# RH020_1.net
KiCad netlist of a schematic drawn in EAGLE
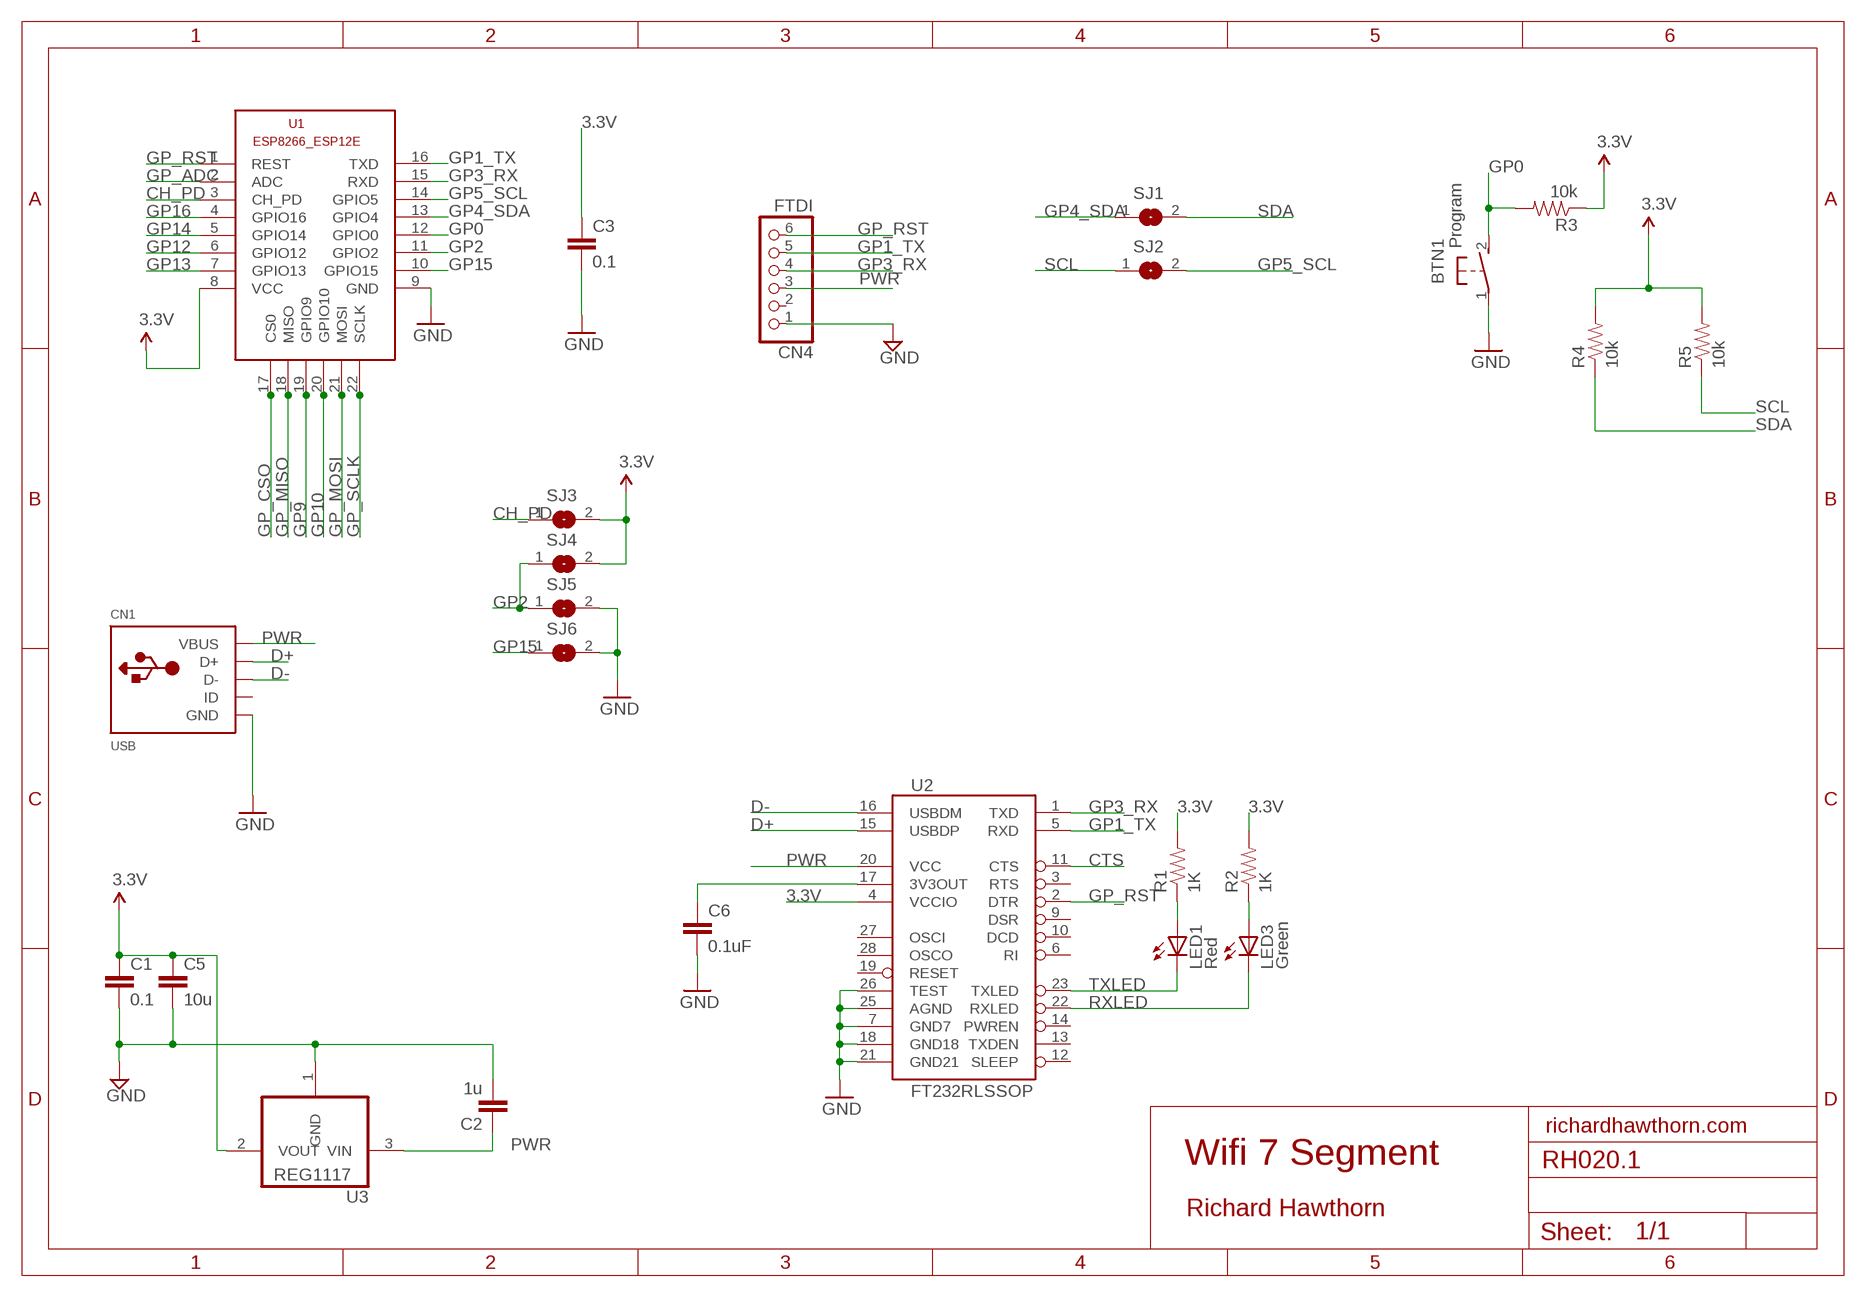
[diagram p0: schematic, sheet 1, part 1 of 2]
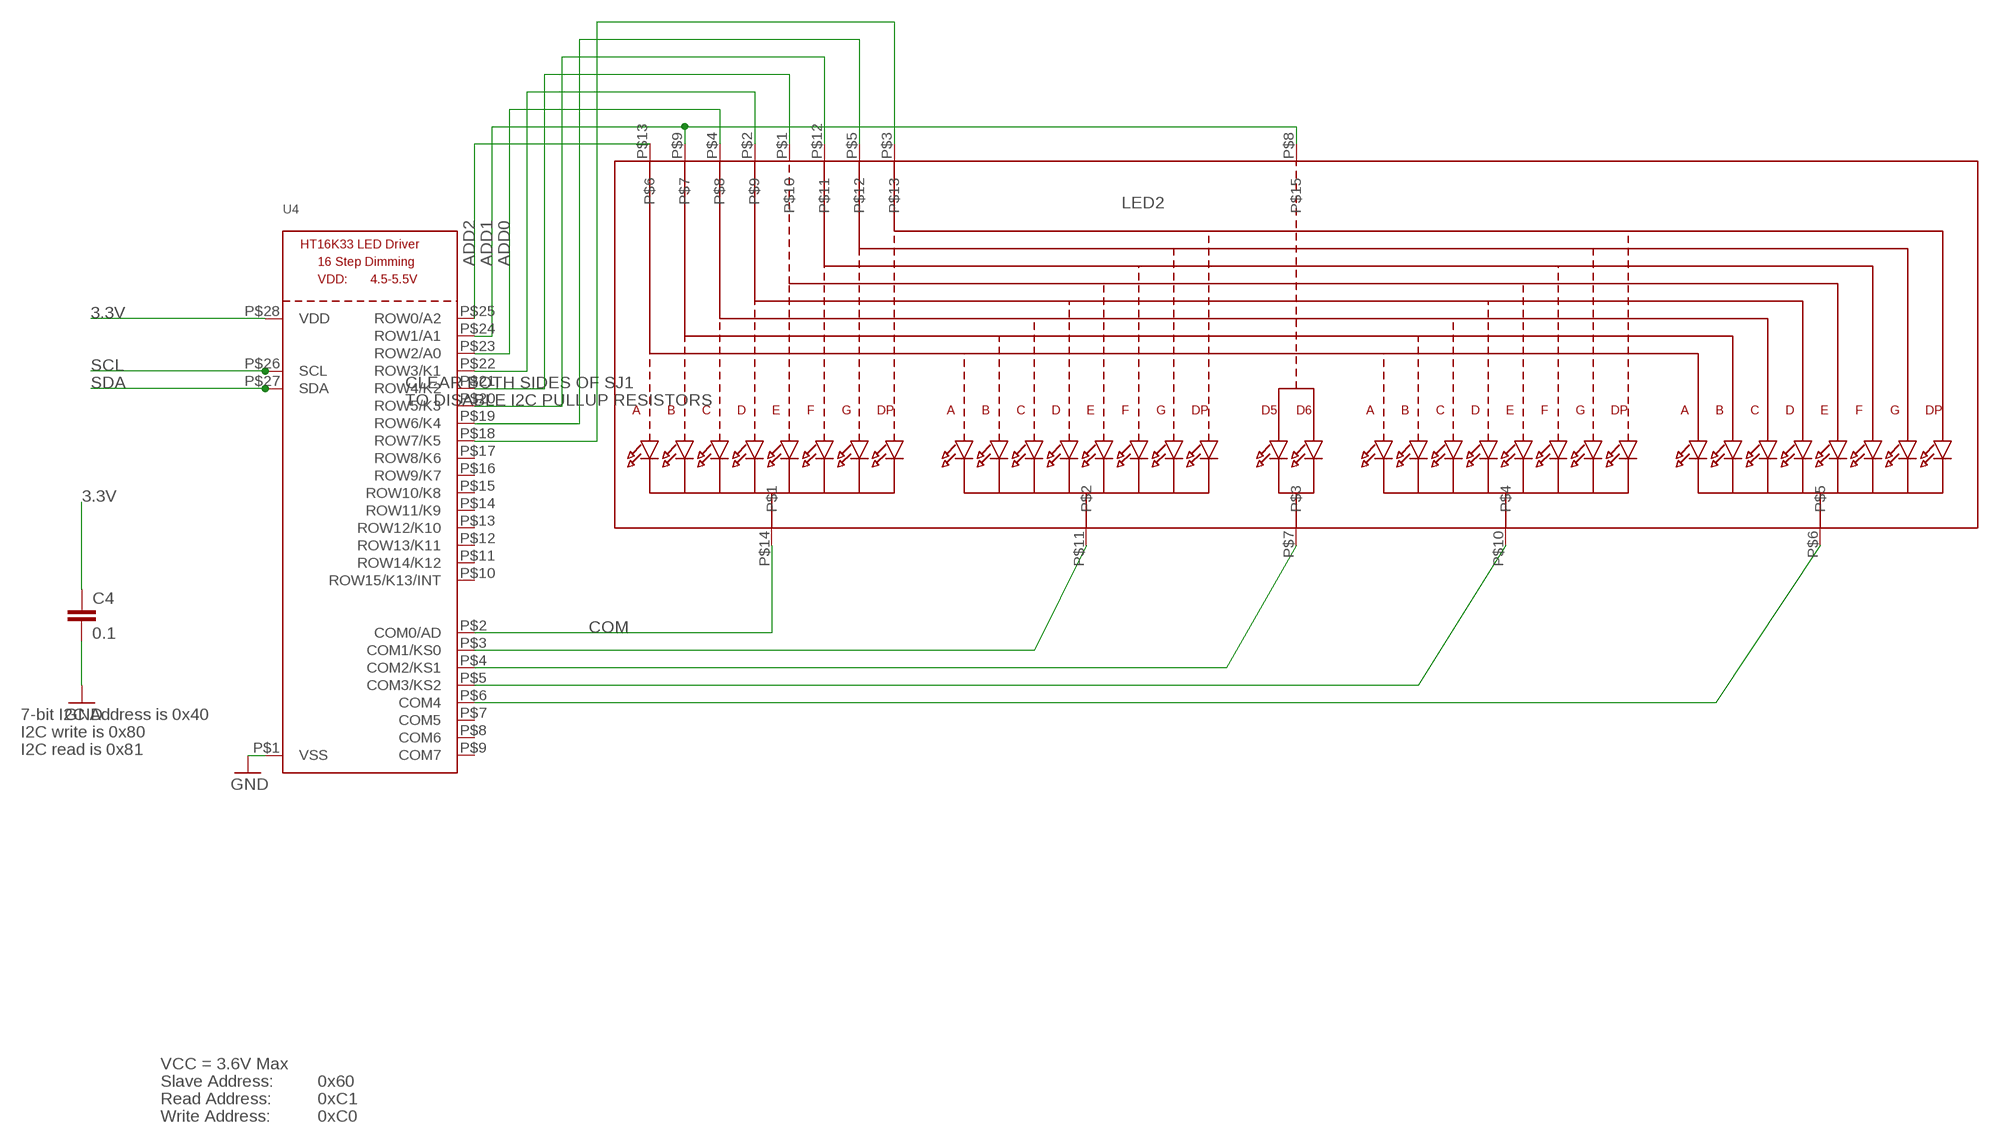
[diagram p1: schematic, sheet 1, part 2 of 2]

(export (version "E")
  (design (tool "Eeschema 10.0.6"))
  (components
    (comp (ref "BTN1")
      (value "Program")
      (footprint "eagle-import:DTS-3")
      (libsource (lib "eagle-import") (part "DTS-3"))
    )
    (comp (ref "C1")
      (value "0.1")
      (footprint "eagle-import:0603-CAP")
      (libsource (lib "eagle-import") (part "CAP0603-CAP"))
    )
    (comp (ref "C2")
      (value "1u")
      (footprint "eagle-import:0603-CAP")
      (libsource (lib "eagle-import") (part "CAP0603-CAP"))
    )
    (comp (ref "C3")
      (value "0.1")
      (footprint "eagle-import:0603-CAP")
      (libsource (lib "eagle-import") (part "CAP0603-CAP"))
    )
    (comp (ref "C4")
      (value "0.1")
      (footprint "eagle-import:0603-CAP")
      (libsource (lib "eagle-import") (part "CAP0603-CAP"))
    )
    (comp (ref "C5")
      (value "10u")
      (footprint "eagle-import:0805-CAP")
      (libsource (lib "eagle-import") (part "CAP0805-CAP"))
    )
    (comp (ref "C6")
      (value "0.1uF")
      (footprint "eagle-import:0402-CAP")
      (libsource (lib "eagle-import") (part "SparkFun_CAP0402-CAP"))
    )
    (comp (ref "CN1")
      (value "USB")
      (footprint "eagle-import:USB-MINIB")
      (libsource (lib "eagle-import") (part "USBMINIB"))
    )
    (comp (ref "CN4")
      (value "FTDI")
      (footprint "eagle-import:1X06")
      (libsource (lib "eagle-import") (part "PINHD-1X6"))
    )
    (comp (ref "LED1")
      (value "Red")
      (footprint "eagle-import:LED-0603")
      (libsource (lib "eagle-import") (part "LED0603"))
    )
    (comp (ref "LED2")
      (value "DISP_SEGMENT_4DIGIT_BL-Q56C43")
      (footprint "eagle-import:SEGMENT-BL-Q56C43")
      (libsource (lib "eagle-import") (part "DISP_SEGMENT_4DIGIT_BL-Q56C43"))
    )
    (comp (ref "LED3")
      (value "Green")
      (footprint "eagle-import:LED-0603")
      (libsource (lib "eagle-import") (part "LED0603"))
    )
    (comp (ref "R1")
      (value "1K")
      (footprint "eagle-import:0402-RES")
      (libsource (lib "eagle-import") (part "RESISTOR0402-RES"))
    )
    (comp (ref "R2")
      (value "1K")
      (footprint "eagle-import:0402-RES")
      (libsource (lib "eagle-import") (part "RESISTOR0402-RES"))
    )
    (comp (ref "R3")
      (value "10k")
      (footprint "eagle-import:0805")
      (libsource (lib "eagle-import") (part "RESISTOR0805-RES"))
    )
    (comp (ref "R4")
      (value "10k")
      (footprint "eagle-import:0805")
      (libsource (lib "eagle-import") (part "RESISTOR0805-RES"))
    )
    (comp (ref "R5")
      (value "10k")
      (footprint "eagle-import:0805")
      (libsource (lib "eagle-import") (part "RESISTOR0805-RES"))
    )
    (comp (ref "SJ1") (value "SJ") (footprint "eagle-import:SJ") (libsource (lib "eagle-import") (part "SJ")))
    (comp (ref "SJ2") (value "SJ") (footprint "eagle-import:SJ") (libsource (lib "eagle-import") (part "SJ")))
    (comp (ref "SJ3") (value "SJ") (footprint "eagle-import:SJ") (libsource (lib "eagle-import") (part "SJ")))
    (comp (ref "SJ4") (value "SJ") (footprint "eagle-import:SJ") (libsource (lib "eagle-import") (part "SJ")))
    (comp (ref "SJ5") (value "SJ") (footprint "eagle-import:SJ") (libsource (lib "eagle-import") (part "SJ")))
    (comp (ref "SJ6") (value "SJ") (footprint "eagle-import:SJ") (libsource (lib "eagle-import") (part "SJ")))
    (comp (ref "U1")
      (value "ESP8266-12EESP8266-ESP12E")
      (footprint "eagle-import:ESP8266-ESP12E")
      (libsource (lib "eagle-import") (part "ESP8266-12EESP8266-ESP12E"))
    )
    (comp (ref "U2")
      (value "FT232RLSSOP")
      (footprint "eagle-import:SSOP28DB")
      (libsource (lib "eagle-import") (part "FT232RLSSOP"))
    )
    (comp (ref "U3")
      (value "REG1117")
      (footprint "eagle-import:SOT223")
      (libsource (lib "eagle-import") (part "REG1117"))
    )
    (comp (ref "U4")
      (value "HT16K33_SOP28")
      (footprint "eagle-import:SOP28_300MIL")
      (libsource (lib "eagle-import") (part "HT16K33_SOP28"))
    )
  )
  (nets
    (net (code "1") (name "/ADD0") (class "Default")
      (node (ref "LED2") (pin "P$4") (pinfunction "P$8_P$4") (pintype "bidirectional"))
      (node (ref "U4") (pin "P$23") (pinfunction "ROW2/A0_P$23") (pintype "bidirectional"))
    )
    (net (code "2") (name "/ADD1") (class "Default")
      (node (ref "LED2") (pin "P$8") (pinfunction "P$15_P$8") (pintype "bidirectional"))
      (node (ref "LED2") (pin "P$9") (pinfunction "P$7_P$9") (pintype "bidirectional"))
      (node (ref "U4") (pin "P$24") (pinfunction "ROW1/A1_P$24") (pintype "bidirectional"))
    )
    (net (code "3") (name "/ADD2") (class "Default")
      (node (ref "LED2") (pin "P$13") (pinfunction "P$6_P$13") (pintype "bidirectional"))
      (node (ref "U4") (pin "P$25") (pinfunction "ROW0/A2_P$25") (pintype "bidirectional"))
    )
    (net (code "4") (name "/CH_PD") (class "Default")
      (node (ref "SJ3") (pin "1") (pinfunction "1_1") (pintype "passive"))
      (node (ref "U1") (pin "3") (pinfunction "CH_PD_3") (pintype "bidirectional"))
    )
    (net (code "5") (name "/COM") (class "Default")
      (node (ref "LED2") (pin "P$14") (pinfunction "P$1_P$14") (pintype "bidirectional"))
      (node (ref "U4") (pin "P$2") (pinfunction "COM0/AD_P$2") (pintype "bidirectional"))
    )
    (net (code "6") (name "/CTS") (class "Default")
      (node (ref "U2") (pin "11") (pinfunction "CTS_11") (pintype "input"))
    )
    (net (code "7") (name "/D+") (class "Default")
      (node (ref "CN1") (pin "D+") (pinfunction "D+_D+") (pintype "bidirectional"))
      (node (ref "U2") (pin "15") (pinfunction "USBDP_15") (pintype "bidirectional"))
    )
    (net (code "8") (name "/D-") (class "Default")
      (node (ref "CN1") (pin "D-") (pinfunction "D-_D-") (pintype "bidirectional"))
      (node (ref "U2") (pin "16") (pinfunction "USBDM_16") (pintype "bidirectional"))
    )
    (net (code "9") (name "/GP0") (class "Default")
      (node (ref "BTN1") (pin "2") (pinfunction "2_2") (pintype "passive"))
      (node (ref "R3") (pin "2") (pinfunction "2_2") (pintype "passive"))
      (node (ref "U1") (pin "12") (pinfunction "GPIO0_12") (pintype "bidirectional"))
    )
    (net (code "10") (name "/GP1_TX") (class "Default")
      (node (ref "CN4") (pin "5") (pinfunction "5_5") (pintype "passive"))
      (node (ref "U1") (pin "16") (pinfunction "TXD_16") (pintype "bidirectional"))
      (node (ref "U2") (pin "5") (pinfunction "RXD_5") (pintype "input"))
    )
    (net (code "11") (name "/GP2") (class "Default")
      (node (ref "SJ4") (pin "1") (pinfunction "1_1") (pintype "passive"))
      (node (ref "SJ5") (pin "1") (pinfunction "1_1") (pintype "passive"))
      (node (ref "U1") (pin "11") (pinfunction "GPIO2_11") (pintype "bidirectional"))
    )
    (net (code "12") (name "/GP3_RX") (class "Default")
      (node (ref "CN4") (pin "4") (pinfunction "4_4") (pintype "passive"))
      (node (ref "U1") (pin "15") (pinfunction "RXD_15") (pintype "bidirectional"))
      (node (ref "U2") (pin "1") (pinfunction "TXD_1") (pintype "output"))
    )
    (net (code "13") (name "/GP4_SDA") (class "Default")
      (node (ref "SJ1") (pin "1") (pinfunction "1_1") (pintype "passive"))
      (node (ref "U1") (pin "13") (pinfunction "GPIO4_13") (pintype "bidirectional"))
    )
    (net (code "14") (name "/GP5_SCL") (class "Default")
      (node (ref "SJ2") (pin "2") (pinfunction "2_2") (pintype "passive"))
      (node (ref "U1") (pin "14") (pinfunction "GPIO5_14") (pintype "bidirectional"))
    )
    (net (code "15") (name "/GP9") (class "Default")
      (node (ref "U1") (pin "19") (pinfunction "GPIO9_19") (pintype "bidirectional"))
    )
    (net (code "16") (name "/GP10") (class "Default")
      (node (ref "U1") (pin "20") (pinfunction "GPIO10_20") (pintype "bidirectional"))
    )
    (net (code "17") (name "/GP12") (class "Default")
      (node (ref "U1") (pin "6") (pinfunction "GPIO12_6") (pintype "bidirectional"))
    )
    (net (code "18") (name "/GP13") (class "Default")
      (node (ref "U1") (pin "7") (pinfunction "GPIO13_7") (pintype "bidirectional"))
    )
    (net (code "19") (name "/GP14") (class "Default")
      (node (ref "U1") (pin "5") (pinfunction "GPIO14_5") (pintype "bidirectional"))
    )
    (net (code "20") (name "/GP15") (class "Default")
      (node (ref "SJ6") (pin "1") (pinfunction "1_1") (pintype "passive"))
      (node (ref "U1") (pin "10") (pinfunction "GPIO15_10") (pintype "bidirectional"))
    )
    (net (code "21") (name "/GP16") (class "Default")
      (node (ref "U1") (pin "4") (pinfunction "GPIO16_4") (pintype "bidirectional"))
    )
    (net (code "22") (name "/GP_ADC") (class "Default")
      (node (ref "U1") (pin "2") (pinfunction "ADC_2") (pintype "bidirectional"))
    )
    (net (code "23") (name "/GP_CSO") (class "Default")
      (node (ref "U1") (pin "17") (pinfunction "CS0_17") (pintype "bidirectional"))
    )
    (net (code "24") (name "/GP_MISO") (class "Default")
      (node (ref "U1") (pin "18") (pinfunction "MISO_18") (pintype "bidirectional"))
    )
    (net (code "25") (name "/GP_MOSI") (class "Default")
      (node (ref "U1") (pin "21") (pinfunction "MOSI_21") (pintype "bidirectional"))
    )
    (net (code "26") (name "/GP_RST") (class "Default")
      (node (ref "CN4") (pin "6") (pinfunction "6_6") (pintype "passive"))
      (node (ref "U1") (pin "1") (pinfunction "REST_1") (pintype "bidirectional"))
      (node (ref "U2") (pin "2") (pinfunction "DTR_2") (pintype "output"))
    )
    (net (code "27") (name "/GP_SCLK") (class "Default")
      (node (ref "U1") (pin "22") (pinfunction "SCLK_22") (pintype "bidirectional"))
    )
    (net (code "28") (name "/PWR") (class "Default")
      (node (ref "C2") (pin "1") (pinfunction "1_1") (pintype "passive"))
      (node (ref "CN1") (pin "VBUS") (pinfunction "VBUS_VBUS") (pintype "power_in"))
      (node (ref "CN4") (pin "3") (pinfunction "3_3") (pintype "passive"))
      (node (ref "U2") (pin "20") (pinfunction "VCC_20") (pintype "power_in"))
      (node (ref "U3") (pin "3") (pinfunction "VIN_3") (pintype "input"))
    )
    (net (code "29") (name "/RXLED") (class "Default")
      (node (ref "LED3") (pin "C") (pinfunction "C_C") (pintype "passive"))
      (node (ref "U2") (pin "22") (pinfunction "RXLED_22") (pintype "input"))
    )
    (net (code "30") (name "/SCL") (class "Default")
      (node (ref "R5") (pin "1") (pinfunction "1_1") (pintype "passive"))
      (node (ref "SJ2") (pin "1") (pinfunction "1_1") (pintype "passive"))
      (node (ref "U4") (pin "P$26") (pinfunction "SCL_P$26") (pintype "bidirectional"))
    )
    (net (code "31") (name "/SDA") (class "Default")
      (node (ref "R4") (pin "1") (pinfunction "1_1") (pintype "passive"))
      (node (ref "SJ1") (pin "2") (pinfunction "2_2") (pintype "passive"))
      (node (ref "U4") (pin "P$27") (pinfunction "SDA_P$27") (pintype "bidirectional"))
    )
    (net (code "32") (name "/TXLED") (class "Default")
      (node (ref "LED1") (pin "C") (pinfunction "C_C") (pintype "passive"))
      (node (ref "U2") (pin "23") (pinfunction "TXLED_23") (pintype "input"))
    )
    (net (code "33") (name "3.3V") (class "Default")
      (node (ref "C1") (pin "1") (pinfunction "1_1") (pintype "passive"))
      (node (ref "C3") (pin "1") (pinfunction "1_1") (pintype "passive"))
      (node (ref "C4") (pin "1") (pinfunction "1_1") (pintype "passive"))
      (node (ref "C5") (pin "1") (pinfunction "1_1") (pintype "passive"))
      (node (ref "R1") (pin "2") (pinfunction "2_2") (pintype "passive"))
      (node (ref "R2") (pin "2") (pinfunction "2_2") (pintype "passive"))
      (node (ref "R3") (pin "1") (pinfunction "1_1") (pintype "passive"))
      (node (ref "R4") (pin "2") (pinfunction "2_2") (pintype "passive"))
      (node (ref "R5") (pin "2") (pinfunction "2_2") (pintype "passive"))
      (node (ref "SJ3") (pin "2") (pinfunction "2_2") (pintype "passive"))
      (node (ref "SJ4") (pin "2") (pinfunction "2_2") (pintype "passive"))
      (node (ref "U1") (pin "8") (pinfunction "VCC_8") (pintype "bidirectional"))
      (node (ref "U2") (pin "4") (pinfunction "VCCIO_4") (pintype "power_in"))
      (node (ref "U3") (pin "2") (pinfunction "VOUT_2") (pintype "output"))
      (node (ref "U4") (pin "P$28") (pinfunction "VDD_P$28") (pintype "bidirectional"))
    )
    (net (code "34") (name "GND") (class "Default")
      (node (ref "BTN1") (pin "1") (pinfunction "1_1") (pintype "passive"))
      (node (ref "C1") (pin "2") (pinfunction "2_2") (pintype "passive"))
      (node (ref "C2") (pin "2") (pinfunction "2_2") (pintype "passive"))
      (node (ref "C3") (pin "2") (pinfunction "2_2") (pintype "passive"))
      (node (ref "C4") (pin "2") (pinfunction "2_2") (pintype "passive"))
      (node (ref "C5") (pin "2") (pinfunction "2_2") (pintype "passive"))
      (node (ref "C6") (pin "2") (pinfunction "2_2") (pintype "passive"))
      (node (ref "CN1") (pin "GND") (pinfunction "GND_GND") (pintype "power_in"))
      (node (ref "CN4") (pin "1") (pinfunction "1_1") (pintype "passive"))
      (node (ref "SJ5") (pin "2") (pinfunction "2_2") (pintype "passive"))
      (node (ref "SJ6") (pin "2") (pinfunction "2_2") (pintype "passive"))
      (node (ref "U1") (pin "9") (pinfunction "GND_9") (pintype "bidirectional"))
      (node (ref "U2") (pin "18") (pinfunction "GND18_18") (pintype "power_in"))
      (node (ref "U2") (pin "21") (pinfunction "GND21_21") (pintype "power_in"))
      (node (ref "U2") (pin "25") (pinfunction "AGND_25") (pintype "power_in"))
      (node (ref "U2") (pin "26") (pinfunction "TEST_26") (pintype "input"))
      (node (ref "U2") (pin "7") (pinfunction "GND7_7") (pintype "power_in"))
      (node (ref "U3") (pin "1") (pinfunction "GND_1") (pintype "power_in"))
      (node (ref "U4") (pin "P$1") (pinfunction "VSS_P$1") (pintype "bidirectional"))
    )
    (net (code "35") (name "Net-(LED1-PadA)") (class "Default")
      (node (ref "LED1") (pin "A") (pinfunction "A_A") (pintype "passive"))
      (node (ref "R1") (pin "1") (pinfunction "1_1") (pintype "passive"))
    )
    (net (code "36") (name "Net-(LED2-P$2)") (class "Default")
      (node (ref "LED2") (pin "P$11") (pinfunction "P$2_P$11") (pintype "bidirectional"))
      (node (ref "U4") (pin "P$3") (pinfunction "COM1/KS0_P$3") (pintype "bidirectional"))
    )
    (net (code "37") (name "Net-(LED2-P$3)") (class "Default")
      (node (ref "LED2") (pin "P$7") (pinfunction "P$3_P$7") (pintype "bidirectional"))
      (node (ref "U4") (pin "P$4") (pinfunction "COM2/KS1_P$4") (pintype "bidirectional"))
    )
    (net (code "38") (name "Net-(LED2-P$4)") (class "Default")
      (node (ref "LED2") (pin "P$10") (pinfunction "P$4_P$10") (pintype "bidirectional"))
      (node (ref "U4") (pin "P$5") (pinfunction "COM3/KS2_P$5") (pintype "bidirectional"))
    )
    (net (code "39") (name "Net-(LED2-P$5)") (class "Default")
      (node (ref "LED2") (pin "P$6") (pinfunction "P$5_P$6") (pintype "bidirectional"))
      (node (ref "U4") (pin "P$6") (pinfunction "COM4_P$6") (pintype "bidirectional"))
    )
    (net (code "40") (name "Net-(LED2-P$9)") (class "Default")
      (node (ref "LED2") (pin "P$2") (pinfunction "P$9_P$2") (pintype "bidirectional"))
      (node (ref "U4") (pin "P$22") (pinfunction "ROW3/K1_P$22") (pintype "bidirectional"))
    )
    (net (code "41") (name "Net-(LED2-P$10)") (class "Default")
      (node (ref "LED2") (pin "P$1") (pinfunction "P$10_P$1") (pintype "bidirectional"))
      (node (ref "U4") (pin "P$21") (pinfunction "ROW4/K2_P$21") (pintype "bidirectional"))
    )
    (net (code "42") (name "Net-(LED2-P$11)") (class "Default")
      (node (ref "LED2") (pin "P$12") (pinfunction "P$11_P$12") (pintype "bidirectional"))
      (node (ref "U4") (pin "P$20") (pinfunction "ROW5/K3_P$20") (pintype "bidirectional"))
    )
    (net (code "43") (name "Net-(LED2-P$12)") (class "Default")
      (node (ref "LED2") (pin "P$5") (pinfunction "P$12_P$5") (pintype "bidirectional"))
      (node (ref "U4") (pin "P$19") (pinfunction "ROW6/K4_P$19") (pintype "bidirectional"))
    )
    (net (code "44") (name "Net-(LED2-P$13)") (class "Default")
      (node (ref "LED2") (pin "P$3") (pinfunction "P$13_P$3") (pintype "bidirectional"))
      (node (ref "U4") (pin "P$18") (pinfunction "ROW7/K5_P$18") (pintype "bidirectional"))
    )
    (net (code "45") (name "Net-(LED3-PadA)") (class "Default")
      (node (ref "LED3") (pin "A") (pinfunction "A_A") (pintype "passive"))
      (node (ref "R2") (pin "1") (pinfunction "1_1") (pintype "passive"))
    )
    (net (code "46") (name "Net-(U2-3V3OUT)") (class "Default")
      (node (ref "C6") (pin "1") (pinfunction "1_1") (pintype "passive"))
      (node (ref "U2") (pin "17") (pinfunction "3V3OUT_17") (pintype "output"))
    )
    (net (code "47") (name "unconnected-(CN1-PadID)") (class "Default")
      (node (ref "CN1") (pin "ID") (pinfunction "ID_ID") (pintype "bidirectional"))
    )
    (net (code "48") (name "unconnected-(CN4-Pad2)") (class "Default")
      (node (ref "CN4") (pin "2") (pinfunction "2_2") (pintype "passive"))
    )
    (net (code "49") (name "unconnected-(U2-DCD-Pad10)") (class "Default")
      (node (ref "U2") (pin "10") (pinfunction "DCD_10") (pintype "input"))
    )
    (net (code "50") (name "unconnected-(U2-DSR-Pad9)") (class "Default")
      (node (ref "U2") (pin "9") (pinfunction "DSR_9") (pintype "input"))
    )
    (net (code "51") (name "unconnected-(U2-OSCI-Pad27)") (class "Default")
      (node (ref "U2") (pin "27") (pinfunction "OSCI_27") (pintype "input"))
    )
    (net (code "52") (name "unconnected-(U2-OSCO-Pad28)") (class "Default")
      (node (ref "U2") (pin "28") (pinfunction "OSCO_28") (pintype "output"))
    )
    (net (code "53") (name "unconnected-(U2-PWREN-Pad14)") (class "Default")
      (node (ref "U2") (pin "14") (pinfunction "PWREN_14") (pintype "input"))
    )
    (net (code "54") (name "unconnected-(U2-RESET-Pad19)") (class "Default")
      (node (ref "U2") (pin "19") (pinfunction "RESET_19") (pintype "input"))
    )
    (net (code "55") (name "unconnected-(U2-RI-Pad6)") (class "Default")
      (node (ref "U2") (pin "6") (pinfunction "RI_6") (pintype "input"))
    )
    (net (code "56") (name "unconnected-(U2-RTS-Pad3)") (class "Default")
      (node (ref "U2") (pin "3") (pinfunction "RTS_3") (pintype "output"))
    )
    (net (code "57") (name "unconnected-(U2-SLEEP-Pad12)") (class "Default")
      (node (ref "U2") (pin "12") (pinfunction "SLEEP_12") (pintype "input"))
    )
    (net (code "58") (name "unconnected-(U2-TXDEN-Pad13)") (class "Default")
      (node (ref "U2") (pin "13") (pinfunction "TXDEN_13") (pintype "input"))
    )
    (net (code "59") (name "unconnected-(U4-COM5-PadP$7)") (class "Default")
      (node (ref "U4") (pin "P$7") (pinfunction "COM5_P$7") (pintype "bidirectional"))
    )
    (net (code "60") (name "unconnected-(U4-COM6-PadP$8)") (class "Default")
      (node (ref "U4") (pin "P$8") (pinfunction "COM6_P$8") (pintype "bidirectional"))
    )
    (net (code "61") (name "unconnected-(U4-COM7-PadP$9)") (class "Default")
      (node (ref "U4") (pin "P$9") (pinfunction "COM7_P$9") (pintype "bidirectional"))
    )
    (net (code "62") (name "unconnected-(U4-ROW8{slash}K6-PadP$17)") (class "Default")
      (node (ref "U4") (pin "P$17") (pinfunction "ROW8/K6_P$17") (pintype "bidirectional"))
    )
    (net (code "63") (name "unconnected-(U4-ROW9{slash}K7-PadP$16)") (class "Default")
      (node (ref "U4") (pin "P$16") (pinfunction "ROW9/K7_P$16") (pintype "bidirectional"))
    )
    (net (code "64") (name "unconnected-(U4-ROW10{slash}K8-PadP$15)") (class "Default")
      (node (ref "U4") (pin "P$15") (pinfunction "ROW10/K8_P$15") (pintype "bidirectional"))
    )
    (net (code "65") (name "unconnected-(U4-ROW11{slash}K9-PadP$14)") (class "Default")
      (node (ref "U4") (pin "P$14") (pinfunction "ROW11/K9_P$14") (pintype "bidirectional"))
    )
    (net (code "66") (name "unconnected-(U4-ROW12{slash}K10-PadP$13)") (class "Default")
      (node (ref "U4") (pin "P$13") (pinfunction "ROW12/K10_P$13") (pintype "bidirectional"))
    )
    (net (code "67") (name "unconnected-(U4-ROW13{slash}K11-PadP$12)") (class "Default")
      (node (ref "U4") (pin "P$12") (pinfunction "ROW13/K11_P$12") (pintype "bidirectional"))
    )
    (net (code "68") (name "unconnected-(U4-ROW14{slash}K12-PadP$11)") (class "Default")
      (node (ref "U4") (pin "P$11") (pinfunction "ROW14/K12_P$11") (pintype "bidirectional"))
    )
    (net (code "69") (name "unconnected-(U4-ROW15{slash}K13{slash}INT-PadP$10)") (class "Default")
      (node (ref "U4") (pin "P$10") (pinfunction "ROW15/K13/INT_P$10") (pintype "bidirectional"))
    )
  )
)
